# My_Smart_Home_Rev2_1.net
KiCad netlist of a schematic drawn in EAGLE
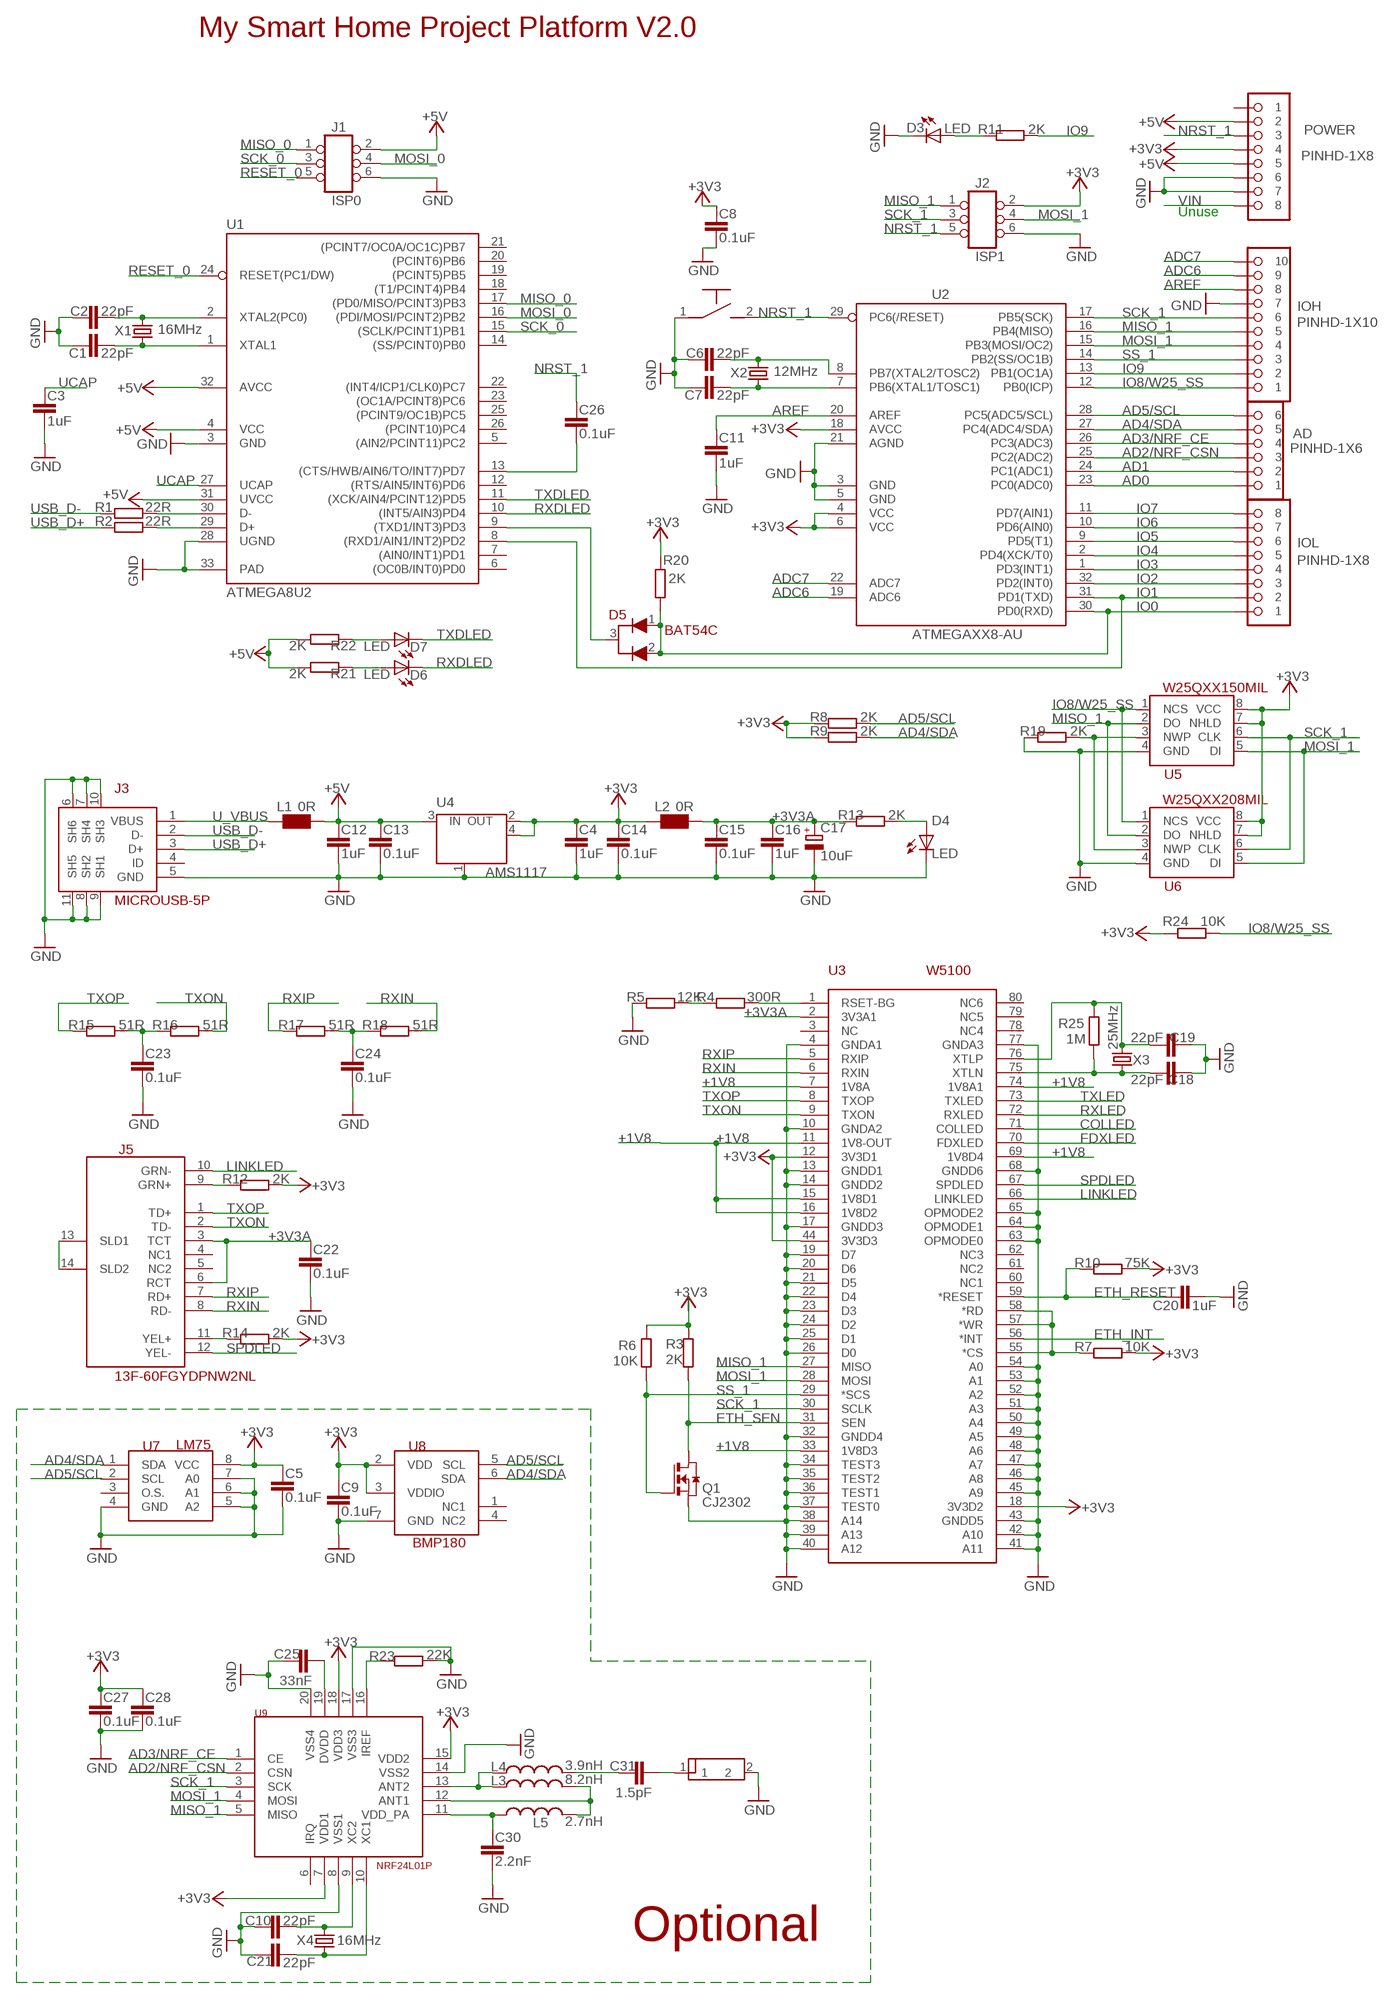
[diagram p0: schematic, sheet 1]

(export (version "E")
  (design (tool "Eeschema 10.0.6"))
  (components
    (comp (ref "AD")
      (value "PINHD-1X6")
      (footprint "eagle-import:1X06")
      (libsource (lib "eagle-import") (part "PINHD-1X6"))
    )
    (comp (ref "ANT1")
      (value "2.4G_ANT1")
      (footprint "eagle-import:2.4G_PCB_ANT")
      (libsource (lib "eagle-import") (part "2.4G_ANT1"))
    )
    (comp (ref "C1")
      (value "22pF")
      (footprint "eagle-import:C0603")
      (libsource (lib "eagle-import") (part "C-NP"))
    )
    (comp (ref "C2")
      (value "22pF")
      (footprint "eagle-import:C0603")
      (libsource (lib "eagle-import") (part "C-NP"))
    )
    (comp (ref "C3")
      (value "1uF")
      (footprint "eagle-import:C0603")
      (libsource (lib "eagle-import") (part "C-NP"))
    )
    (comp (ref "C4")
      (value "1uF")
      (footprint "eagle-import:C0603")
      (libsource (lib "eagle-import") (part "C-NP"))
    )
    (comp (ref "C5")
      (value "0.1uF")
      (footprint "eagle-import:C0603")
      (libsource (lib "eagle-import") (part "C-NP"))
    )
    (comp (ref "C6")
      (value "22pF")
      (footprint "eagle-import:C0603")
      (libsource (lib "eagle-import") (part "C-NP"))
    )
    (comp (ref "C7")
      (value "22pF")
      (footprint "eagle-import:C0603")
      (libsource (lib "eagle-import") (part "C-NP"))
    )
    (comp (ref "C8")
      (value "0.1uF")
      (footprint "eagle-import:C0603")
      (libsource (lib "eagle-import") (part "C-NP"))
    )
    (comp (ref "C9")
      (value "0.1uF")
      (footprint "eagle-import:C0603")
      (libsource (lib "eagle-import") (part "C-NP"))
    )
    (comp (ref "C10")
      (value "22pF")
      (footprint "eagle-import:C0603")
      (libsource (lib "eagle-import") (part "C-NP"))
    )
    (comp (ref "C11")
      (value "1uF")
      (footprint "eagle-import:C0603")
      (libsource (lib "eagle-import") (part "C-NP"))
    )
    (comp (ref "C12")
      (value "1uF")
      (footprint "eagle-import:C0603")
      (libsource (lib "eagle-import") (part "C-NP"))
    )
    (comp (ref "C13")
      (value "0.1uF")
      (footprint "eagle-import:C0603")
      (libsource (lib "eagle-import") (part "C-NP"))
    )
    (comp (ref "C14")
      (value "0.1uF")
      (footprint "eagle-import:C0603")
      (libsource (lib "eagle-import") (part "C-NP"))
    )
    (comp (ref "C15")
      (value "0.1uF")
      (footprint "eagle-import:C0603")
      (libsource (lib "eagle-import") (part "C-NP"))
    )
    (comp (ref "C16")
      (value "1uF")
      (footprint "eagle-import:C0603")
      (libsource (lib "eagle-import") (part "C-NP"))
    )
    (comp (ref "C17")
      (value "10uF")
      (footprint "eagle-import:C0805")
      (libsource (lib "eagle-import") (part "C-POL"))
    )
    (comp (ref "C18")
      (value "22pF")
      (footprint "eagle-import:C0603")
      (libsource (lib "eagle-import") (part "C-NP"))
    )
    (comp (ref "C19")
      (value "22pF")
      (footprint "eagle-import:C0603")
      (libsource (lib "eagle-import") (part "C-NP"))
    )
    (comp (ref "C20")
      (value "1uF")
      (footprint "eagle-import:C0603")
      (libsource (lib "eagle-import") (part "C-NP"))
    )
    (comp (ref "C21")
      (value "22pF")
      (footprint "eagle-import:C0603")
      (libsource (lib "eagle-import") (part "C-NP"))
    )
    (comp (ref "C22")
      (value "0.1uF")
      (footprint "eagle-import:C0603")
      (libsource (lib "eagle-import") (part "C-NP"))
    )
    (comp (ref "C23")
      (value "0.1uF")
      (footprint "eagle-import:C0603")
      (libsource (lib "eagle-import") (part "C-NP"))
    )
    (comp (ref "C24")
      (value "0.1uF")
      (footprint "eagle-import:C0603")
      (libsource (lib "eagle-import") (part "C-NP"))
    )
    (comp (ref "C25")
      (value "33nF")
      (footprint "eagle-import:C0603")
      (libsource (lib "eagle-import") (part "C-NP"))
    )
    (comp (ref "C26")
      (value "0.1uF")
      (footprint "eagle-import:C0603")
      (libsource (lib "eagle-import") (part "C-NP"))
    )
    (comp (ref "C27")
      (value "0.1uF")
      (footprint "eagle-import:C0603")
      (libsource (lib "eagle-import") (part "C-NP"))
    )
    (comp (ref "C28")
      (value "0.1uF")
      (footprint "eagle-import:C0603")
      (libsource (lib "eagle-import") (part "C-NP"))
    )
    (comp (ref "C30")
      (value "2.2nF")
      (footprint "eagle-import:C0603")
      (libsource (lib "eagle-import") (part "C-NP"))
    )
    (comp (ref "C31")
      (value "1.5pF")
      (footprint "eagle-import:C0603")
      (libsource (lib "eagle-import") (part "C-NP"))
    )
    (comp (ref "D3")
      (value "LED")
      (footprint "eagle-import:LED0805")
      (libsource (lib "eagle-import") (part "LED"))
    )
    (comp (ref "D4")
      (value "LED")
      (footprint "eagle-import:LED0805")
      (libsource (lib "eagle-import") (part "LED"))
    )
    (comp (ref "D5")
      (value "BAT54C")
      (footprint "eagle-import:SOT23")
      (libsource (lib "eagle-import") (part "BAT54C"))
    )
    (comp (ref "D6")
      (value "LED")
      (footprint "eagle-import:LED0805")
      (libsource (lib "eagle-import") (part "LED"))
    )
    (comp (ref "D7")
      (value "LED")
      (footprint "eagle-import:LED0805")
      (libsource (lib "eagle-import") (part "LED"))
    )
    (comp (ref "IOH")
      (value "PINHD-1X10")
      (footprint "eagle-import:1X10")
      (libsource (lib "eagle-import") (part "PINHD-1X10"))
    )
    (comp (ref "IOL")
      (value "PINHD-1X8")
      (footprint "eagle-import:1X08")
      (libsource (lib "eagle-import") (part "PINHD-1X8"))
    )
    (comp (ref "J1")
      (value "ISP0")
      (footprint "eagle-import:2X03")
      (libsource (lib "eagle-import") (part "PINHD-2X3"))
    )
    (comp (ref "J2")
      (value "ISP1")
      (footprint "eagle-import:2X03")
      (libsource (lib "eagle-import") (part "PINHD-2X3"))
    )
    (comp (ref "J3")
      (value "MICROUSB-5P")
      (footprint "eagle-import:MICROUSB-5P-SMD")
      (libsource (lib "eagle-import") (part "MICROUSB-5P"))
    )
    (comp (ref "J5")
      (value "13F-60FGYDPNW2NL")
      (footprint "eagle-import:13F-60FGYDPNW2NL")
      (libsource (lib "eagle-import") (part "13F-60FGYDPNW2NL"))
    )
    (comp (ref "L1")
      (value "0R")
      (footprint "eagle-import:R0603")
      (libsource (lib "eagle-import") (part "L_M"))
    )
    (comp (ref "L2")
      (value "0R")
      (footprint "eagle-import:R0603")
      (libsource (lib "eagle-import") (part "L_M"))
    )
    (comp (ref "L3")
      (value "8.2nH")
      (footprint "eagle-import:R0603")
      (libsource (lib "eagle-import") (part "L"))
    )
    (comp (ref "L4")
      (value "3.9nH")
      (footprint "eagle-import:R0603")
      (libsource (lib "eagle-import") (part "L"))
    )
    (comp (ref "L5")
      (value "2.7nH")
      (footprint "eagle-import:R0603")
      (libsource (lib "eagle-import") (part "L"))
    )
    (comp (ref "POWER")
      (value "PINHD-1X8")
      (footprint "eagle-import:1X08")
      (libsource (lib "eagle-import") (part "PINHD-1X8"))
    )
    (comp (ref "Q1")
      (value "CJ2302")
      (footprint "eagle-import:SOT23")
      (libsource (lib "eagle-import") (part "NMOS-SOT23"))
    )
    (comp (ref "R1")
      (value "22R")
      (footprint "eagle-import:R0603")
      (libsource (lib "eagle-import") (part "RES"))
    )
    (comp (ref "R2")
      (value "22R")
      (footprint "eagle-import:R0603")
      (libsource (lib "eagle-import") (part "RES"))
    )
    (comp (ref "R3")
      (value "2K")
      (footprint "eagle-import:R0603")
      (libsource (lib "eagle-import") (part "RES"))
    )
    (comp (ref "R4")
      (value "300R")
      (footprint "eagle-import:R0603")
      (libsource (lib "eagle-import") (part "RES"))
    )
    (comp (ref "R5")
      (value "12K")
      (footprint "eagle-import:R0603")
      (libsource (lib "eagle-import") (part "RES"))
    )
    (comp (ref "R6")
      (value "10K")
      (footprint "eagle-import:R0603")
      (libsource (lib "eagle-import") (part "RES"))
    )
    (comp (ref "R7")
      (value "10K")
      (footprint "eagle-import:R0603")
      (libsource (lib "eagle-import") (part "RES"))
    )
    (comp (ref "R8")
      (value "2K")
      (footprint "eagle-import:R0603")
      (libsource (lib "eagle-import") (part "RES"))
    )
    (comp (ref "R9")
      (value "2K")
      (footprint "eagle-import:R0603")
      (libsource (lib "eagle-import") (part "RES"))
    )
    (comp (ref "R10")
      (value "75K")
      (footprint "eagle-import:R0603")
      (libsource (lib "eagle-import") (part "RES"))
    )
    (comp (ref "R11")
      (value "2K")
      (footprint "eagle-import:R0603")
      (libsource (lib "eagle-import") (part "RES"))
    )
    (comp (ref "R12")
      (value "2K")
      (footprint "eagle-import:R0603")
      (libsource (lib "eagle-import") (part "RES"))
    )
    (comp (ref "R13")
      (value "2K")
      (footprint "eagle-import:R0603")
      (libsource (lib "eagle-import") (part "RES"))
    )
    (comp (ref "R14")
      (value "2K")
      (footprint "eagle-import:R0603")
      (libsource (lib "eagle-import") (part "RES"))
    )
    (comp (ref "R15")
      (value "51R")
      (footprint "eagle-import:R0603")
      (libsource (lib "eagle-import") (part "RES"))
    )
    (comp (ref "R16")
      (value "51R")
      (footprint "eagle-import:R0603")
      (libsource (lib "eagle-import") (part "RES"))
    )
    (comp (ref "R17")
      (value "51R")
      (footprint "eagle-import:R0603")
      (libsource (lib "eagle-import") (part "RES"))
    )
    (comp (ref "R18")
      (value "51R")
      (footprint "eagle-import:R0603")
      (libsource (lib "eagle-import") (part "RES"))
    )
    (comp (ref "R19")
      (value "2K")
      (footprint "eagle-import:R0603")
      (libsource (lib "eagle-import") (part "RES"))
    )
    (comp (ref "R20")
      (value "2K")
      (footprint "eagle-import:R0603")
      (libsource (lib "eagle-import") (part "RES"))
    )
    (comp (ref "R21")
      (value "2K")
      (footprint "eagle-import:R0603")
      (libsource (lib "eagle-import") (part "RES"))
    )
    (comp (ref "R22")
      (value "2K")
      (footprint "eagle-import:R0603")
      (libsource (lib "eagle-import") (part "RES"))
    )
    (comp (ref "R23")
      (value "22K")
      (footprint "eagle-import:R0603")
      (libsource (lib "eagle-import") (part "RES"))
    )
    (comp (ref "R24")
      (value "10K")
      (footprint "eagle-import:R0603")
      (libsource (lib "eagle-import") (part "RES"))
    )
    (comp (ref "R25")
      (value "1M")
      (footprint "eagle-import:R0603")
      (libsource (lib "eagle-import") (part "RES"))
    )
    (comp (ref "SW2")
      (value "SW-2")
      (footprint "eagle-import:SW-2P-SMD")
      (libsource (lib "eagle-import") (part "SW-2"))
    )
    (comp (ref "U1")
      (value "ATMEGA8U2")
      (footprint "eagle-import:MLF32")
      (libsource (lib "eagle-import") (part "ATMEGA8U2"))
    )
    (comp (ref "U2")
      (value "ATMEGAXX8-AU")
      (footprint "eagle-import:TQFP32-08")
      (libsource (lib "eagle-import") (part "ATMEGAXX8-AU"))
    )
    (comp (ref "U3")
      (value "W5100")
      (footprint "eagle-import:SQFP-S-10X10-80")
      (libsource (lib "eagle-import") (part "W5100"))
    )
    (comp (ref "U4")
      (value "AMS1117")
      (footprint "eagle-import:SOT223")
      (libsource (lib "eagle-import") (part "AMS1117"))
    )
    (comp (ref "U5")
      (value "W25QXX150MIL")
      (footprint "eagle-import:8S1")
      (libsource (lib "eagle-import") (part "W25QXX150MIL"))
    )
    (comp (ref "U6")
      (value "W25QXX208MIL")
      (footprint "eagle-import:8S2")
      (libsource (lib "eagle-import") (part "W25QXX208MIL"))
    )
    (comp (ref "U7")
      (value "LM75")
      (footprint "eagle-import:8S1")
      (libsource (lib "eagle-import") (part "LM75"))
    )
    (comp (ref "U8")
      (value "BMP180")
      (footprint "eagle-import:LGA-7P")
      (libsource (lib "eagle-import") (part "BMP180"))
    )
    (comp (ref "U9")
      (value "NRF24L01P")
      (footprint "eagle-import:QFN20")
      (libsource (lib "eagle-import") (part "NRF24L01P"))
    )
    (comp (ref "X1")
      (value "16MHz")
      (footprint "eagle-import:HC49UP")
      (libsource (lib "eagle-import") (part "CRYSTAL"))
    )
    (comp (ref "X2")
      (value "12MHz")
      (footprint "eagle-import:HC49UP")
      (libsource (lib "eagle-import") (part "CRYSTAL"))
    )
    (comp (ref "X3")
      (value "25MHz")
      (footprint "eagle-import:HC49UP")
      (libsource (lib "eagle-import") (part "CRYSTAL"))
    )
    (comp (ref "X4")
      (value "16MHz")
      (footprint "eagle-import:HC49UP")
      (libsource (lib "eagle-import") (part "CRYSTAL"))
    )
  )
  (nets
    (net (code "1") (name "+3V3") (class "Default")
      (node (ref "C14") (pin "2") (pinfunction "2_2") (pintype "passive"))
      (node (ref "C27") (pin "2") (pinfunction "2_2") (pintype "passive"))
      (node (ref "C28") (pin "2") (pinfunction "2_2") (pintype "passive"))
      (node (ref "C4") (pin "2") (pinfunction "2_2") (pintype "passive"))
      (node (ref "C5") (pin "2") (pinfunction "2_2") (pintype "passive"))
      (node (ref "C8") (pin "2") (pinfunction "2_2") (pintype "passive"))
      (node (ref "C9") (pin "2") (pinfunction "2_2") (pintype "passive"))
      (node (ref "J2") (pin "2") (pinfunction "2_2") (pintype "passive"))
      (node (ref "L2") (pin "1") (pinfunction "1_1") (pintype "passive"))
      (node (ref "POWER") (pin "4") (pinfunction "4_4") (pintype "passive"))
      (node (ref "R10") (pin "2") (pinfunction "2_2") (pintype "passive"))
      (node (ref "R12") (pin "1") (pinfunction "1_1") (pintype "passive"))
      (node (ref "R14") (pin "1") (pinfunction "1_1") (pintype "passive"))
      (node (ref "R20") (pin "2") (pinfunction "2_2") (pintype "passive"))
      (node (ref "R24") (pin "1") (pinfunction "1_1") (pintype "passive"))
      (node (ref "R3") (pin "2") (pinfunction "2_2") (pintype "passive"))
      (node (ref "R6") (pin "1") (pinfunction "1_1") (pintype "passive"))
      (node (ref "R7") (pin "2") (pinfunction "2_2") (pintype "passive"))
      (node (ref "R8") (pin "2") (pinfunction "2_2") (pintype "passive"))
      (node (ref "R9") (pin "2") (pinfunction "2_2") (pintype "passive"))
      (node (ref "U2") (pin "18") (pinfunction "AVCC_18") (pintype "bidirectional"))
      (node (ref "U2") (pin "4") (pinfunction "VCC_4") (pintype "bidirectional"))
      (node (ref "U2") (pin "6") (pinfunction "VCC_6") (pintype "bidirectional"))
      (node (ref "U3") (pin "12") (pinfunction "3V3D1_12") (pintype "power_in"))
      (node (ref "U3") (pin "18") (pinfunction "3V3D2_18") (pintype "power_in"))
      (node (ref "U3") (pin "44") (pinfunction "3V3D3_44") (pintype "power_in"))
      (node (ref "U4") (pin "2") (pinfunction "OUT_2") (pintype "passive"))
      (node (ref "U4") (pin "4") (pinfunction "OUT_4") (pintype "passive"))
      (node (ref "U5") (pin "7") (pinfunction "NHLD_7") (pintype "bidirectional"))
      (node (ref "U5") (pin "8") (pinfunction "VCC_8") (pintype "bidirectional"))
      (node (ref "U6") (pin "7") (pinfunction "NHLD_7") (pintype "bidirectional"))
      (node (ref "U6") (pin "8") (pinfunction "VCC_8") (pintype "bidirectional"))
      (node (ref "U7") (pin "8") (pinfunction "VCC_8") (pintype "bidirectional"))
      (node (ref "U8") (pin "2") (pinfunction "VDD_2") (pintype "bidirectional"))
      (node (ref "U8") (pin "3") (pinfunction "VDDIO_3") (pintype "bidirectional"))
      (node (ref "U9") (pin "15") (pinfunction "VDD2_15") (pintype "bidirectional"))
      (node (ref "U9") (pin "18") (pinfunction "VDD3_18") (pintype "bidirectional"))
      (node (ref "U9") (pin "7") (pinfunction "VDD1_7") (pintype "bidirectional"))
    )
    (net (code "2") (name "+5V") (class "Default")
      (node (ref "C12") (pin "2") (pinfunction "2_2") (pintype "passive"))
      (node (ref "C13") (pin "2") (pinfunction "2_2") (pintype "passive"))
      (node (ref "J1") (pin "2") (pinfunction "2_2") (pintype "passive"))
      (node (ref "L1") (pin "2") (pinfunction "2_2") (pintype "passive"))
      (node (ref "POWER") (pin "2") (pinfunction "2_2") (pintype "passive"))
      (node (ref "POWER") (pin "5") (pinfunction "5_5") (pintype "passive"))
      (node (ref "R21") (pin "1") (pinfunction "1_1") (pintype "passive"))
      (node (ref "R22") (pin "1") (pinfunction "1_1") (pintype "passive"))
      (node (ref "U1") (pin "31") (pinfunction "UVCC_31") (pintype "power_in"))
      (node (ref "U1") (pin "32") (pinfunction "AVCC_32") (pintype "power_in"))
      (node (ref "U1") (pin "4") (pinfunction "VCC_4") (pintype "power_in"))
      (node (ref "U4") (pin "3") (pinfunction "IN_3") (pintype "input"))
    )
    (net (code "3") (name "/+1V8") (class "Default")
      (node (ref "U3") (pin "11") (pinfunction "1V8-OUT_11") (pintype "power_in"))
      (node (ref "U3") (pin "15") (pinfunction "1V8D1_15") (pintype "power_in"))
      (node (ref "U3") (pin "16") (pinfunction "1V8D2_16") (pintype "power_in"))
      (node (ref "U3") (pin "33") (pinfunction "1V8D3_33") (pintype "power_in"))
      (node (ref "U3") (pin "69") (pinfunction "1V8D4_69") (pintype "power_in"))
      (node (ref "U3") (pin "7") (pinfunction "1V8A_7") (pintype "power_in"))
      (node (ref "U3") (pin "74") (pinfunction "1V8A1_74") (pintype "power_in"))
    )
    (net (code "4") (name "/+3V3A") (class "Default")
      (node (ref "C15") (pin "2") (pinfunction "2_2") (pintype "passive"))
      (node (ref "C16") (pin "2") (pinfunction "2_2") (pintype "passive"))
      (node (ref "C17") (pin "1") (pinfunction "+_1") (pintype "passive"))
      (node (ref "C22") (pin "2") (pinfunction "2_2") (pintype "passive"))
      (node (ref "J5") (pin "3") (pinfunction "TCT_3") (pintype "bidirectional"))
      (node (ref "J5") (pin "6") (pinfunction "RCT_6") (pintype "bidirectional"))
      (node (ref "L2") (pin "2") (pinfunction "2_2") (pintype "passive"))
      (node (ref "R13") (pin "2") (pinfunction "2_2") (pintype "passive"))
      (node (ref "U3") (pin "2") (pinfunction "3V3A1_2") (pintype "power_in"))
    )
    (net (code "5") (name "/AD0") (class "Default")
      (node (ref "AD") (pin "1") (pinfunction "1_1") (pintype "passive"))
      (node (ref "U2") (pin "23") (pinfunction "PC0(ADC0)_23") (pintype "bidirectional"))
    )
    (net (code "6") (name "/AD1") (class "Default")
      (node (ref "AD") (pin "2") (pinfunction "2_2") (pintype "passive"))
      (node (ref "U2") (pin "24") (pinfunction "PC1(ADC1)_24") (pintype "bidirectional"))
    )
    (net (code "7") (name "/AD2{slash}NRF_CSN") (class "Default")
      (node (ref "AD") (pin "3") (pinfunction "3_3") (pintype "passive"))
      (node (ref "U2") (pin "25") (pinfunction "PC2(ADC2)_25") (pintype "bidirectional"))
      (node (ref "U9") (pin "2") (pinfunction "CSN_2") (pintype "bidirectional"))
    )
    (net (code "8") (name "/AD3{slash}NRF_CE") (class "Default")
      (node (ref "AD") (pin "4") (pinfunction "4_4") (pintype "passive"))
      (node (ref "U2") (pin "26") (pinfunction "PC3(ADC3)_26") (pintype "bidirectional"))
      (node (ref "U9") (pin "1") (pinfunction "CE_1") (pintype "bidirectional"))
    )
    (net (code "9") (name "/AD4{slash}SDA") (class "Default")
      (node (ref "AD") (pin "5") (pinfunction "5_5") (pintype "passive"))
      (node (ref "R9") (pin "1") (pinfunction "1_1") (pintype "passive"))
      (node (ref "U2") (pin "27") (pinfunction "PC4(ADC4/SDA)_27") (pintype "bidirectional"))
      (node (ref "U7") (pin "1") (pinfunction "SDA_1") (pintype "bidirectional"))
      (node (ref "U8") (pin "6") (pinfunction "SDA_6") (pintype "bidirectional"))
    )
    (net (code "10") (name "/AD5{slash}SCL") (class "Default")
      (node (ref "AD") (pin "6") (pinfunction "6_6") (pintype "passive"))
      (node (ref "R8") (pin "1") (pinfunction "1_1") (pintype "passive"))
      (node (ref "U2") (pin "28") (pinfunction "PC5(ADC5/SCL)_28") (pintype "bidirectional"))
      (node (ref "U7") (pin "2") (pinfunction "SCL_2") (pintype "bidirectional"))
      (node (ref "U8") (pin "5") (pinfunction "SCL_5") (pintype "bidirectional"))
    )
    (net (code "11") (name "/ADC6") (class "Default")
      (node (ref "IOH") (pin "9") (pinfunction "9_9") (pintype "passive"))
      (node (ref "U2") (pin "19") (pinfunction "ADC6_19") (pintype "bidirectional"))
    )
    (net (code "12") (name "/ADC7") (class "Default")
      (node (ref "IOH") (pin "10") (pinfunction "10_10") (pintype "passive"))
      (node (ref "U2") (pin "22") (pinfunction "ADC7_22") (pintype "bidirectional"))
    )
    (net (code "13") (name "/AREF") (class "Default")
      (node (ref "C11") (pin "2") (pinfunction "2_2") (pintype "passive"))
      (node (ref "IOH") (pin "8") (pinfunction "8_8") (pintype "passive"))
      (node (ref "U2") (pin "20") (pinfunction "AREF_20") (pintype "bidirectional"))
    )
    (net (code "14") (name "/COLLED") (class "Default")
      (node (ref "U3") (pin "71") (pinfunction "COLLED_71") (pintype "output"))
    )
    (net (code "15") (name "/ETH_INT") (class "Default")
      (node (ref "U3") (pin "56") (pinfunction "*INT_56") (pintype "input"))
    )
    (net (code "16") (name "/ETH_RESET") (class "Default")
      (node (ref "C20") (pin "2") (pinfunction "2_2") (pintype "passive"))
      (node (ref "R10") (pin "1") (pinfunction "1_1") (pintype "passive"))
      (node (ref "U3") (pin "59") (pinfunction "*RESET_59") (pintype "input"))
    )
    (net (code "17") (name "/ETH_SEN") (class "Default")
      (node (ref "Q1") (pin "3") (pinfunction "D_3") (pintype "passive"))
      (node (ref "R3") (pin "1") (pinfunction "1_1") (pintype "passive"))
      (node (ref "U3") (pin "31") (pinfunction "SEN_31") (pintype "input"))
    )
    (net (code "18") (name "/FDXLED") (class "Default")
      (node (ref "U3") (pin "70") (pinfunction "FDXLED_70") (pintype "output"))
    )
    (net (code "19") (name "/IO0") (class "Default")
      (node (ref "D5") (pin "1") (pinfunction "1_1") (pintype "bidirectional"))
      (node (ref "D5") (pin "2") (pinfunction "2_2") (pintype "bidirectional"))
      (node (ref "IOL") (pin "1") (pinfunction "1_1") (pintype "passive"))
      (node (ref "R20") (pin "1") (pinfunction "1_1") (pintype "passive"))
      (node (ref "U2") (pin "30") (pinfunction "PD0(RXD)_30") (pintype "bidirectional"))
    )
    (net (code "20") (name "/IO1") (class "Default")
      (node (ref "IOL") (pin "2") (pinfunction "2_2") (pintype "passive"))
      (node (ref "U1") (pin "8") (pinfunction "(RXD1/AIN1/INT2)PD2_8") (pintype "bidirectional"))
      (node (ref "U2") (pin "31") (pinfunction "PD1(TXD)_31") (pintype "bidirectional"))
    )
    (net (code "21") (name "/IO2") (class "Default")
      (node (ref "IOL") (pin "3") (pinfunction "3_3") (pintype "passive"))
      (node (ref "U2") (pin "32") (pinfunction "PD2(INT0)_32") (pintype "bidirectional"))
    )
    (net (code "22") (name "/IO3") (class "Default")
      (node (ref "IOL") (pin "4") (pinfunction "4_4") (pintype "passive"))
      (node (ref "U2") (pin "1") (pinfunction "PD3(INT1)_1") (pintype "bidirectional"))
    )
    (net (code "23") (name "/IO4") (class "Default")
      (node (ref "IOL") (pin "5") (pinfunction "5_5") (pintype "passive"))
      (node (ref "U2") (pin "2") (pinfunction "PD4(XCK/T0)_2") (pintype "bidirectional"))
    )
    (net (code "24") (name "/IO5") (class "Default")
      (node (ref "IOL") (pin "6") (pinfunction "6_6") (pintype "passive"))
      (node (ref "U2") (pin "9") (pinfunction "PD5(T1)_9") (pintype "bidirectional"))
    )
    (net (code "25") (name "/IO6") (class "Default")
      (node (ref "IOL") (pin "7") (pinfunction "7_7") (pintype "passive"))
      (node (ref "U2") (pin "10") (pinfunction "PD6(AIN0)_10") (pintype "bidirectional"))
    )
    (net (code "26") (name "/IO7") (class "Default")
      (node (ref "IOL") (pin "8") (pinfunction "8_8") (pintype "passive"))
      (node (ref "U2") (pin "11") (pinfunction "PD7(AIN1)_11") (pintype "bidirectional"))
    )
    (net (code "27") (name "/IO8{slash}W25_SS") (class "Default")
      (node (ref "IOH") (pin "1") (pinfunction "1_1") (pintype "passive"))
      (node (ref "R24") (pin "2") (pinfunction "2_2") (pintype "passive"))
      (node (ref "U2") (pin "12") (pinfunction "PB0(ICP)_12") (pintype "bidirectional"))
      (node (ref "U5") (pin "1") (pinfunction "NCS_1") (pintype "bidirectional"))
      (node (ref "U6") (pin "1") (pinfunction "NCS_1") (pintype "bidirectional"))
    )
    (net (code "28") (name "/IO9") (class "Default")
      (node (ref "IOH") (pin "2") (pinfunction "2_2") (pintype "passive"))
      (node (ref "R11") (pin "1") (pinfunction "1_1") (pintype "passive"))
      (node (ref "U2") (pin "13") (pinfunction "PB1(OC1A)_13") (pintype "bidirectional"))
    )
    (net (code "29") (name "/LINKLED") (class "Default")
      (node (ref "J5") (pin "10") (pinfunction "GRN-_10") (pintype "bidirectional"))
      (node (ref "U3") (pin "66") (pinfunction "LINKLED_66") (pintype "output"))
    )
    (net (code "30") (name "/MISO_0") (class "Default")
      (node (ref "J1") (pin "1") (pinfunction "1_1") (pintype "passive"))
      (node (ref "U1") (pin "17") (pinfunction "(PD0/MISO/PCINT3)PB3_17") (pintype "bidirectional"))
    )
    (net (code "31") (name "/MISO_1") (class "Default")
      (node (ref "IOH") (pin "5") (pinfunction "5_5") (pintype "passive"))
      (node (ref "J2") (pin "1") (pinfunction "1_1") (pintype "passive"))
      (node (ref "U2") (pin "16") (pinfunction "PB4(MISO)_16") (pintype "bidirectional"))
      (node (ref "U3") (pin "27") (pinfunction "MISO_27") (pintype "input"))
      (node (ref "U5") (pin "2") (pinfunction "DO_2") (pintype "bidirectional"))
      (node (ref "U6") (pin "2") (pinfunction "DO_2") (pintype "bidirectional"))
      (node (ref "U9") (pin "5") (pinfunction "MISO_5") (pintype "bidirectional"))
    )
    (net (code "32") (name "/MOSI_0") (class "Default")
      (node (ref "J1") (pin "4") (pinfunction "4_4") (pintype "passive"))
      (node (ref "U1") (pin "16") (pinfunction "(PDI/MOSI/PCINT2)PB2_16") (pintype "bidirectional"))
    )
    (net (code "33") (name "/MOSI_1") (class "Default")
      (node (ref "IOH") (pin "4") (pinfunction "4_4") (pintype "passive"))
      (node (ref "J2") (pin "4") (pinfunction "4_4") (pintype "passive"))
      (node (ref "U2") (pin "15") (pinfunction "PB3(MOSI/OC2)_15") (pintype "bidirectional"))
      (node (ref "U3") (pin "28") (pinfunction "MOSI_28") (pintype "output"))
      (node (ref "U5") (pin "5") (pinfunction "DI_5") (pintype "bidirectional"))
      (node (ref "U6") (pin "5") (pinfunction "DI_5") (pintype "bidirectional"))
      (node (ref "U9") (pin "4") (pinfunction "MOSI_4") (pintype "bidirectional"))
    )
    (net (code "34") (name "/NRST_1") (class "Default")
      (node (ref "C26") (pin "2") (pinfunction "2_2") (pintype "passive"))
      (node (ref "J2") (pin "5") (pinfunction "5_5") (pintype "passive"))
      (node (ref "POWER") (pin "3") (pinfunction "3_3") (pintype "passive"))
      (node (ref "SW2") (pin "2") (pinfunction "P$2_2") (pintype "bidirectional"))
      (node (ref "U2") (pin "29") (pinfunction "PC6(/RESET)_29") (pintype "bidirectional"))
    )
    (net (code "35") (name "/RESET_0") (class "Default")
      (node (ref "J1") (pin "5") (pinfunction "5_5") (pintype "passive"))
      (node (ref "U1") (pin "24") (pinfunction "RESET(PC1/DW)_24") (pintype "input"))
    )
    (net (code "36") (name "/RXDLED") (class "Default")
      (node (ref "D6") (pin "C") (pinfunction "C_C") (pintype "passive"))
      (node (ref "U1") (pin "10") (pinfunction "(INT5/AIN3)PD4_10") (pintype "bidirectional"))
    )
    (net (code "37") (name "/RXIN") (class "Default")
      (node (ref "J5") (pin "8") (pinfunction "RD-_8") (pintype "bidirectional"))
      (node (ref "R18") (pin "1") (pinfunction "1_1") (pintype "passive"))
      (node (ref "U3") (pin "6") (pinfunction "RXIN_6") (pintype "input"))
    )
    (net (code "38") (name "/RXIP") (class "Default")
      (node (ref "J5") (pin "7") (pinfunction "RD+_7") (pintype "bidirectional"))
      (node (ref "R17") (pin "2") (pinfunction "2_2") (pintype "passive"))
      (node (ref "U3") (pin "5") (pinfunction "RXIP_5") (pintype "input"))
    )
    (net (code "39") (name "/RXLED") (class "Default")
      (node (ref "U3") (pin "72") (pinfunction "RXLED_72") (pintype "output"))
    )
    (net (code "40") (name "/SCK_0") (class "Default")
      (node (ref "J1") (pin "3") (pinfunction "3_3") (pintype "passive"))
      (node (ref "U1") (pin "15") (pinfunction "(SCLK/PCINT1)PB1_15") (pintype "bidirectional"))
    )
    (net (code "41") (name "/SCK_1") (class "Default")
      (node (ref "IOH") (pin "6") (pinfunction "6_6") (pintype "passive"))
      (node (ref "J2") (pin "3") (pinfunction "3_3") (pintype "passive"))
      (node (ref "U2") (pin "17") (pinfunction "PB5(SCK)_17") (pintype "bidirectional"))
      (node (ref "U3") (pin "30") (pinfunction "SCLK_30") (pintype "input"))
      (node (ref "U5") (pin "6") (pinfunction "CLK_6") (pintype "bidirectional"))
      (node (ref "U6") (pin "6") (pinfunction "CLK_6") (pintype "bidirectional"))
      (node (ref "U9") (pin "3") (pinfunction "SCK_3") (pintype "bidirectional"))
    )
    (net (code "42") (name "/SPDLED") (class "Default")
      (node (ref "J5") (pin "12") (pinfunction "YEL-_12") (pintype "bidirectional"))
      (node (ref "U3") (pin "67") (pinfunction "SPDLED_67") (pintype "output"))
    )
    (net (code "43") (name "/SS_1") (class "Default")
      (node (ref "IOH") (pin "3") (pinfunction "3_3") (pintype "passive"))
      (node (ref "Q1") (pin "1") (pinfunction "G_1") (pintype "passive"))
      (node (ref "R6") (pin "2") (pinfunction "2_2") (pintype "passive"))
      (node (ref "U2") (pin "14") (pinfunction "PB2(SS/OC1B)_14") (pintype "bidirectional"))
      (node (ref "U3") (pin "29") (pinfunction "*SCS_29") (pintype "input"))
    )
    (net (code "44") (name "/TXDLED") (class "Default")
      (node (ref "D7") (pin "C") (pinfunction "C_C") (pintype "passive"))
      (node (ref "U1") (pin "11") (pinfunction "(XCK/AIN4/PCINT12)PD5_11") (pintype "bidirectional"))
    )
    (net (code "45") (name "/TXLED") (class "Default")
      (node (ref "U3") (pin "73") (pinfunction "TXLED_73") (pintype "output"))
    )
    (net (code "46") (name "/TXON") (class "Default")
      (node (ref "J5") (pin "2") (pinfunction "TD-_2") (pintype "bidirectional"))
      (node (ref "R16") (pin "1") (pinfunction "1_1") (pintype "passive"))
      (node (ref "U3") (pin "9") (pinfunction "TXON_9") (pintype "output"))
    )
    (net (code "47") (name "/TXOP") (class "Default")
      (node (ref "J5") (pin "1") (pinfunction "TD+_1") (pintype "bidirectional"))
      (node (ref "R15") (pin "2") (pinfunction "2_2") (pintype "passive"))
      (node (ref "U3") (pin "8") (pinfunction "TXOP_8") (pintype "output"))
    )
    (net (code "48") (name "/UCAP") (class "Default")
      (node (ref "C3") (pin "2") (pinfunction "2_2") (pintype "passive"))
      (node (ref "U1") (pin "27") (pinfunction "UCAP_27") (pintype "passive"))
    )
    (net (code "49") (name "/USB_D+") (class "Default")
      (node (ref "J3") (pin "3") (pinfunction "D+_3") (pintype "bidirectional"))
      (node (ref "R2") (pin "1") (pinfunction "1_1") (pintype "passive"))
    )
    (net (code "50") (name "/USB_D-") (class "Default")
      (node (ref "J3") (pin "2") (pinfunction "D-_2") (pintype "bidirectional"))
      (node (ref "R1") (pin "1") (pinfunction "1_1") (pintype "passive"))
    )
    (net (code "51") (name "/U_VBUS") (class "Default")
      (node (ref "J3") (pin "1") (pinfunction "VBUS_1") (pintype "bidirectional"))
      (node (ref "L1") (pin "1") (pinfunction "1_1") (pintype "passive"))
    )
    (net (code "52") (name "/VIN") (class "Default")
      (node (ref "POWER") (pin "8") (pinfunction "8_8") (pintype "passive"))
    )
    (net (code "53") (name "GND") (class "Default")
      (node (ref "ANT1") (pin "2") (pinfunction "2_2") (pintype "bidirectional"))
      (node (ref "C1") (pin "1") (pinfunction "1_1") (pintype "passive"))
      (node (ref "C10") (pin "1") (pinfunction "1_1") (pintype "passive"))
      (node (ref "C11") (pin "1") (pinfunction "1_1") (pintype "passive"))
      (node (ref "C12") (pin "1") (pinfunction "1_1") (pintype "passive"))
      (node (ref "C13") (pin "1") (pinfunction "1_1") (pintype "passive"))
      (node (ref "C14") (pin "1") (pinfunction "1_1") (pintype "passive"))
      (node (ref "C15") (pin "1") (pinfunction "1_1") (pintype "passive"))
      (node (ref "C16") (pin "1") (pinfunction "1_1") (pintype "passive"))
      (node (ref "C17") (pin "2") (pinfunction "-_2") (pintype "passive"))
      (node (ref "C18") (pin "1") (pinfunction "1_1") (pintype "passive"))
      (node (ref "C19") (pin "1") (pinfunction "1_1") (pintype "passive"))
      (node (ref "C2") (pin "1") (pinfunction "1_1") (pintype "passive"))
      (node (ref "C20") (pin "1") (pinfunction "1_1") (pintype "passive"))
      (node (ref "C21") (pin "1") (pinfunction "1_1") (pintype "passive"))
      (node (ref "C22") (pin "1") (pinfunction "1_1") (pintype "passive"))
      (node (ref "C23") (pin "1") (pinfunction "1_1") (pintype "passive"))
      (node (ref "C24") (pin "1") (pinfunction "1_1") (pintype "passive"))
      (node (ref "C25") (pin "2") (pinfunction "2_2") (pintype "passive"))
      (node (ref "C27") (pin "1") (pinfunction "1_1") (pintype "passive"))
      (node (ref "C28") (pin "1") (pinfunction "1_1") (pintype "passive"))
      (node (ref "C3") (pin "1") (pinfunction "1_1") (pintype "passive"))
      (node (ref "C30") (pin "1") (pinfunction "1_1") (pintype "passive"))
      (node (ref "C4") (pin "1") (pinfunction "1_1") (pintype "passive"))
      (node (ref "C5") (pin "1") (pinfunction "1_1") (pintype "passive"))
      (node (ref "C6") (pin "1") (pinfunction "1_1") (pintype "passive"))
      (node (ref "C7") (pin "1") (pinfunction "1_1") (pintype "passive"))
      (node (ref "C8") (pin "1") (pinfunction "1_1") (pintype "passive"))
      (node (ref "C9") (pin "1") (pinfunction "1_1") (pintype "passive"))
      (node (ref "D3") (pin "C") (pinfunction "C_C") (pintype "passive"))
      (node (ref "D4") (pin "C") (pinfunction "C_C") (pintype "passive"))
      (node (ref "IOH") (pin "7") (pinfunction "7_7") (pintype "passive"))
      (node (ref "J1") (pin "6") (pinfunction "6_6") (pintype "passive"))
      (node (ref "J2") (pin "6") (pinfunction "6_6") (pintype "passive"))
      (node (ref "J3") (pin "10") (pinfunction "SH3_10") (pintype "bidirectional"))
      (node (ref "J3") (pin "11") (pinfunction "SH5_11") (pintype "bidirectional"))
      (node (ref "J3") (pin "5") (pinfunction "GND_5") (pintype "bidirectional"))
      (node (ref "J3") (pin "6") (pinfunction "SH6_6") (pintype "bidirectional"))
      (node (ref "J3") (pin "7") (pinfunction "SH4_7") (pintype "bidirectional"))
      (node (ref "J3") (pin "8") (pinfunction "SH2_8") (pintype "bidirectional"))
      (node (ref "J3") (pin "9") (pinfunction "SH1_9") (pintype "bidirectional"))
      (node (ref "POWER") (pin "6") (pinfunction "6_6") (pintype "passive"))
      (node (ref "POWER") (pin "7") (pinfunction "7_7") (pintype "passive"))
      (node (ref "Q1") (pin "2") (pinfunction "S_2") (pintype "passive"))
      (node (ref "R19") (pin "2") (pinfunction "2_2") (pintype "passive"))
      (node (ref "R23") (pin "1") (pinfunction "1_1") (pintype "passive"))
      (node (ref "R5") (pin "1") (pinfunction "1_1") (pintype "passive"))
      (node (ref "SW2") (pin "1") (pinfunction "P$1_1") (pintype "bidirectional"))
      (node (ref "U1") (pin "28") (pinfunction "UGND_28") (pintype "power_in"))
      (node (ref "U1") (pin "3") (pinfunction "GND_3") (pintype "power_in"))
      (node (ref "U1") (pin "33") (pinfunction "PAD_33") (pintype "power_in"))
      (node (ref "U2") (pin "21") (pinfunction "AGND_21") (pintype "bidirectional"))
      (node (ref "U2") (pin "3") (pinfunction "GND_3") (pintype "bidirectional"))
      (node (ref "U2") (pin "5") (pinfunction "GND_5") (pintype "bidirectional"))
      (node (ref "U3") (pin "10") (pinfunction "GNDA2_10") (pintype "power_in"))
      (node (ref "U3") (pin "13") (pinfunction "GNDD1_13") (pintype "power_in"))
      (node (ref "U3") (pin "14") (pinfunction "GNDD2_14") (pintype "power_in"))
      (node (ref "U3") (pin "17") (pinfunction "GNDD3_17") (pintype "power_in"))
      (node (ref "U3") (pin "19") (pinfunction "D7_19") (pintype "input"))
      (node (ref "U3") (pin "20") (pinfunction "D6_20") (pintype "input"))
      (node (ref "U3") (pin "21") (pinfunction "D5_21") (pintype "input"))
      (node (ref "U3") (pin "22") (pinfunction "D4_22") (pintype "input"))
      (node (ref "U3") (pin "23") (pinfunction "D3_23") (pintype "input"))
      (node (ref "U3") (pin "24") (pinfunction "D2_24") (pintype "input"))
      (node (ref "U3") (pin "25") (pinfunction "D1_25") (pintype "input"))
      (node (ref "U3") (pin "26") (pinfunction "D0_26") (pintype "input"))
      (node (ref "U3") (pin "32") (pinfunction "GNDD4_32") (pintype "power_in"))
      (node (ref "U3") (pin "34") (pinfunction "TEST3_34") (pintype "input"))
      (node (ref "U3") (pin "35") (pinfunction "TEST2_35") (pintype "input"))
      (node (ref "U3") (pin "36") (pinfunction "TEST1_36") (pintype "input"))
      (node (ref "U3") (pin "37") (pinfunction "TEST0_37") (pintype "input"))
      (node (ref "U3") (pin "38") (pinfunction "A14_38") (pintype "input"))
      (node (ref "U3") (pin "39") (pinfunction "A13_39") (pintype "input"))
      (node (ref "U3") (pin "4") (pinfunction "GNDA1_4") (pintype "power_in"))
      (node (ref "U3") (pin "40") (pinfunction "A12_40") (pintype "input"))
      (node (ref "U3") (pin "41") (pinfunction "A11_41") (pintype "input"))
      (node (ref "U3") (pin "42") (pinfunction "A10_42") (pintype "input"))
      (node (ref "U3") (pin "43") (pinfunction "GNDD5_43") (pintype "power_in"))
      (node (ref "U3") (pin "45") (pinfunction "A9_45") (pintype "input"))
      (node (ref "U3") (pin "46") (pinfunction "A8_46") (pintype "input"))
      (node (ref "U3") (pin "47") (pinfunction "A7_47") (pintype "input"))
      (node (ref "U3") (pin "48") (pinfunction "A6_48") (pintype "input"))
      (node (ref "U3") (pin "49") (pinfunction "A5_49") (pintype "input"))
      (node (ref "U3") (pin "50") (pinfunction "A4_50") (pintype "input"))
      (node (ref "U3") (pin "51") (pinfunction "A3_51") (pintype "input"))
      (node (ref "U3") (pin "52") (pinfunction "A2_52") (pintype "input"))
      (node (ref "U3") (pin "53") (pinfunction "A1_53") (pintype "input"))
      (node (ref "U3") (pin "54") (pinfunction "A0_54") (pintype "input"))
      (node (ref "U3") (pin "63") (pinfunction "OPMODE0_63") (pintype "input"))
      (node (ref "U3") (pin "64") (pinfunction "OPMODE1_64") (pintype "input"))
      (node (ref "U3") (pin "65") (pinfunction "OPMODE2_65") (pintype "input"))
      (node (ref "U3") (pin "68") (pinfunction "GNDD6_68") (pintype "power_in"))
      (node (ref "U3") (pin "77") (pinfunction "GNDA3_77") (pintype "power_in"))
      (node (ref "U4") (pin "1") (pinfunction "GND/ADJ_1") (pintype "input"))
      (node (ref "U5") (pin "4") (pinfunction "GND_4") (pintype "bidirectional"))
      (node (ref "U6") (pin "4") (pinfunction "GND_4") (pintype "bidirectional"))
      (node (ref "U7") (pin "4") (pinfunction "GND_4") (pintype "bidirectional"))
      (node (ref "U7") (pin "5") (pinfunction "A2_5") (pintype "bidirectional"))
      (node (ref "U7") (pin "6") (pinfunction "A1_6") (pintype "bidirectional"))
      (node (ref "U7") (pin "7") (pinfunction "A0_7") (pintype "bidirectional"))
      (node (ref "U8") (pin "7") (pinfunction "GND_7") (pintype "bidirectional"))
      (node (ref "U9") (pin "14") (pinfunction "VSS2_14") (pintype "bidirectional"))
      (node (ref "U9") (pin "17") (pinfunction "VSS3_17") (pintype "bidirectional"))
      (node (ref "U9") (pin "20") (pinfunction "VSS4_20") (pintype "bidirectional"))
      (node (ref "U9") (pin "8") (pinfunction "VSS1_8") (pintype "bidirectional"))
    )
    (net (code "54") (name "Net-(ANT1-Pad1)") (class "Default")
      (node (ref "ANT1") (pin "1") (pinfunction "1_1") (pintype "bidirectional"))
      (node (ref "C31") (pin "1") (pinfunction "1_1") (pintype "passive"))
    )
    (net (code "55") (name "Net-(C23-Pad2)") (class "Default")
      (node (ref "C23") (pin "2") (pinfunction "2_2") (pintype "passive"))
      (node (ref "R15") (pin "1") (pinfunction "1_1") (pintype "passive"))
      (node (ref "R16") (pin "2") (pinfunction "2_2") (pintype "passive"))
    )
    (net (code "56") (name "Net-(C24-Pad2)") (class "Default")
      (node (ref "C24") (pin "2") (pinfunction "2_2") (pintype "passive"))
      (node (ref "R17") (pin "1") (pinfunction "1_1") (pintype "passive"))
      (node (ref "R18") (pin "2") (pinfunction "2_2") (pintype "passive"))
    )
    (net (code "57") (name "Net-(C31-Pad2)") (class "Default")
      (node (ref "C31") (pin "2") (pinfunction "2_2") (pintype "passive"))
      (node (ref "L4") (pin "2") (pinfunction "2_2") (pintype "passive"))
    )
    (net (code "58") (name "Net-(D3-PadA)") (class "Default")
      (node (ref "D3") (pin "A") (pinfunction "A_A") (pintype "passive"))
      (node (ref "R11") (pin "2") (pinfunction "2_2") (pintype "passive"))
    )
    (net (code "59") (name "Net-(D4-PadA)") (class "Default")
      (node (ref "D4") (pin "A") (pinfunction "A_A") (pintype "passive"))
      (node (ref "R13") (pin "1") (pinfunction "1_1") (pintype "passive"))
    )
    (net (code "60") (name "Net-(D6-PadA)") (class "Default")
      (node (ref "D6") (pin "A") (pinfunction "A_A") (pintype "passive"))
      (node (ref "R21") (pin "2") (pinfunction "2_2") (pintype "passive"))
    )
    (net (code "61") (name "Net-(D7-PadA)") (class "Default")
      (node (ref "D7") (pin "A") (pinfunction "A_A") (pintype "passive"))
      (node (ref "R22") (pin "2") (pinfunction "2_2") (pintype "passive"))
    )
    (net (code "62") (name "Net-(J5-GRN+)") (class "Default")
      (node (ref "J5") (pin "9") (pinfunction "GRN+_9") (pintype "bidirectional"))
      (node (ref "R12") (pin "2") (pinfunction "2_2") (pintype "passive"))
    )
    (net (code "63") (name "Net-(J5-SLD1)") (class "Default")
      (node (ref "J5") (pin "13") (pinfunction "SLD1_13") (pintype "bidirectional"))
      (node (ref "J5") (pin "14") (pinfunction "SLD2_14") (pintype "bidirectional"))
    )
    (net (code "64") (name "Net-(J5-YEL+)") (class "Default")
      (node (ref "J5") (pin "11") (pinfunction "YEL+_11") (pintype "bidirectional"))
      (node (ref "R14") (pin "2") (pinfunction "2_2") (pintype "passive"))
    )
    (net (code "65") (name "Net-(R4-Pad1)") (class "Default")
      (node (ref "R4") (pin "1") (pinfunction "1_1") (pintype "passive"))
      (node (ref "R5") (pin "2") (pinfunction "2_2") (pintype "passive"))
    )
    (net (code "66") (name "Net-(U1-(CTS{slash}HWB{slash}AIN6{slash}TO{slash}INT7)PD7)") (class "Default")
      (node (ref "C26") (pin "1") (pinfunction "1_1") (pintype "passive"))
      (node (ref "U1") (pin "13") (pinfunction "(CTS/HWB/AIN6/TO/INT7)PD7_13") (pintype "bidirectional"))
    )
    (net (code "67") (name "Net-(U1-(TXD1{slash}INT3)PD3)") (class "Default")
      (node (ref "D5") (pin "3") (pinfunction "3_3") (pintype "bidirectional"))
      (node (ref "U1") (pin "9") (pinfunction "(TXD1/INT3)PD3_9") (pintype "bidirectional"))
    )
    (net (code "68") (name "Net-(U1-D+)") (class "Default")
      (node (ref "R2") (pin "2") (pinfunction "2_2") (pintype "passive"))
      (node (ref "U1") (pin "29") (pinfunction "D+_29") (pintype "bidirectional"))
    )
    (net (code "69") (name "Net-(U1-D-)") (class "Default")
      (node (ref "R1") (pin "2") (pinfunction "2_2") (pintype "passive"))
      (node (ref "U1") (pin "30") (pinfunction "D-_30") (pintype "bidirectional"))
    )
    (net (code "70") (name "Net-(U1-XTAL1)") (class "Default")
      (node (ref "C1") (pin "2") (pinfunction "2_2") (pintype "passive"))
      (node (ref "U1") (pin "1") (pinfunction "XTAL1_1") (pintype "bidirectional"))
      (node (ref "X1") (pin "1") (pinfunction "1_1") (pintype "passive"))
    )
    (net (code "71") (name "Net-(U1-XTAL2(PC0))") (class "Default")
      (node (ref "C2") (pin "2") (pinfunction "2_2") (pintype "passive"))
      (node (ref "U1") (pin "2") (pinfunction "XTAL2(PC0)_2") (pintype "bidirectional"))
      (node (ref "X1") (pin "2") (pinfunction "2_2") (pintype "passive"))
    )
    (net (code "72") (name "Net-(U2-PB6(XTAL1{slash}TOSC1))") (class "Default")
      (node (ref "C7") (pin "2") (pinfunction "2_2") (pintype "passive"))
      (node (ref "U2") (pin "7") (pinfunction "PB6(XTAL1/TOSC1)_7") (pintype "bidirectional"))
      (node (ref "X2") (pin "1") (pinfunction "1_1") (pintype "passive"))
    )
    (net (code "73") (name "Net-(U2-PB7(XTAL2{slash}TOSC2))") (class "Default")
      (node (ref "C6") (pin "2") (pinfunction "2_2") (pintype "passive"))
      (node (ref "U2") (pin "8") (pinfunction "PB7(XTAL2/TOSC2)_8") (pintype "bidirectional"))
      (node (ref "X2") (pin "2") (pinfunction "2_2") (pintype "passive"))
    )
    (net (code "74") (name "Net-(U3-*CS)") (class "Default")
      (node (ref "R7") (pin "1") (pinfunction "1_1") (pintype "passive"))
      (node (ref "U3") (pin "55") (pinfunction "*CS_55") (pintype "input"))
      (node (ref "U3") (pin "57") (pinfunction "*WR_57") (pintype "input"))
      (node (ref "U3") (pin "58") (pinfunction "*RD_58") (pintype "input"))
    )
    (net (code "75") (name "Net-(U3-RSET-BG)") (class "Default")
      (node (ref "R4") (pin "2") (pinfunction "2_2") (pintype "passive"))
      (node (ref "U3") (pin "1") (pinfunction "RSET-BG_1") (pintype "input"))
    )
    (net (code "76") (name "Net-(U3-XTLN)") (class "Default")
      (node (ref "C18") (pin "2") (pinfunction "2_2") (pintype "passive"))
      (node (ref "R25") (pin "2") (pinfunction "2_2") (pintype "passive"))
      (node (ref "U3") (pin "75") (pinfunction "XTLN_75") (pintype "output"))
      (node (ref "X3") (pin "2") (pinfunction "2_2") (pintype "passive"))
    )
    (net (code "77") (name "Net-(U3-XTLP)") (class "Default")
      (node (ref "C19") (pin "2") (pinfunction "2_2") (pintype "passive"))
      (node (ref "R25") (pin "1") (pinfunction "1_1") (pintype "passive"))
      (node (ref "U3") (pin "76") (pinfunction "XTLP_76") (pintype "output"))
      (node (ref "X3") (pin "1") (pinfunction "1_1") (pintype "passive"))
    )
    (net (code "78") (name "Net-(U5-NWP)") (class "Default")
      (node (ref "R19") (pin "1") (pinfunction "1_1") (pintype "passive"))
      (node (ref "U5") (pin "3") (pinfunction "NWP_3") (pintype "bidirectional"))
      (node (ref "U6") (pin "3") (pinfunction "NWP_3") (pintype "bidirectional"))
    )
    (net (code "79") (name "Net-(U9-ANT1)") (class "Default")
      (node (ref "L3") (pin "2") (pinfunction "2_2") (pintype "passive"))
      (node (ref "L5") (pin "2") (pinfunction "2_2") (pintype "passive"))
      (node (ref "U9") (pin "12") (pinfunction "ANT1_12") (pintype "bidirectional"))
    )
    (net (code "80") (name "Net-(U9-ANT2)") (class "Default")
      (node (ref "L3") (pin "1") (pinfunction "1_1") (pintype "passive"))
      (node (ref "L4") (pin "1") (pinfunction "1_1") (pintype "passive"))
      (node (ref "U9") (pin "13") (pinfunction "ANT2_13") (pintype "bidirectional"))
    )
    (net (code "81") (name "Net-(U9-DVDD)") (class "Default")
      (node (ref "C25") (pin "1") (pinfunction "1_1") (pintype "passive"))
      (node (ref "U9") (pin "19") (pinfunction "DVDD_19") (pintype "bidirectional"))
    )
    (net (code "82") (name "Net-(U9-IREF)") (class "Default")
      (node (ref "R23") (pin "2") (pinfunction "2_2") (pintype "passive"))
      (node (ref "U9") (pin "16") (pinfunction "IREF_16") (pintype "bidirectional"))
    )
    (net (code "83") (name "Net-(U9-VDD_PA)") (class "Default")
      (node (ref "C30") (pin "2") (pinfunction "2_2") (pintype "passive"))
      (node (ref "L5") (pin "1") (pinfunction "1_1") (pintype "passive"))
      (node (ref "U9") (pin "11") (pinfunction "VDD_PA_11") (pintype "bidirectional"))
    )
    (net (code "84") (name "Net-(U9-XC1)") (class "Default")
      (node (ref "C21") (pin "2") (pinfunction "2_2") (pintype "passive"))
      (node (ref "U9") (pin "10") (pinfunction "XC1_10") (pintype "bidirectional"))
      (node (ref "X4") (pin "1") (pinfunction "1_1") (pintype "passive"))
    )
    (net (code "85") (name "Net-(U9-XC2)") (class "Default")
      (node (ref "C10") (pin "2") (pinfunction "2_2") (pintype "passive"))
      (node (ref "U9") (pin "9") (pinfunction "XC2_9") (pintype "bidirectional"))
      (node (ref "X4") (pin "2") (pinfunction "2_2") (pintype "passive"))
    )
    (net (code "86") (name "unconnected-(J3-ID-Pad4)") (class "Default")
      (node (ref "J3") (pin "4") (pinfunction "ID_4") (pintype "bidirectional"))
    )
    (net (code "87") (name "unconnected-(J5-NC1-Pad4)") (class "Default")
      (node (ref "J5") (pin "4") (pinfunction "NC1_4") (pintype "bidirectional"))
    )
    (net (code "88") (name "unconnected-(J5-NC2-Pad5)") (class "Default")
      (node (ref "J5") (pin "5") (pinfunction "NC2_5") (pintype "bidirectional"))
    )
    (net (code "89") (name "unconnected-(POWER-Pad1)") (class "Default")
      (node (ref "POWER") (pin "1") (pinfunction "1_1") (pintype "passive"))
    )
    (net (code "90") (name "unconnected-(U1-(AIN0{slash}INT1)PD1-Pad7)") (class "Default")
      (node (ref "U1") (pin "7") (pinfunction "(AIN0/INT1)PD1_7") (pintype "bidirectional"))
    )
    (net (code "91") (name "unconnected-(U1-(AIN2{slash}PCINT11)PC2-Pad5)") (class "Default")
      (node (ref "U1") (pin "5") (pinfunction "(AIN2/PCINT11)PC2_5") (pintype "bidirectional"))
    )
    (net (code "92") (name "unconnected-(U1-(INT4{slash}ICP1{slash}CLK0)PC7-Pad22)") (class "Default")
      (node (ref "U1") (pin "22") (pinfunction "(INT4/ICP1/CLK0)PC7_22") (pintype "bidirectional"))
    )
    (net (code "93") (name "unconnected-(U1-(OC0B{slash}INT0)PD0-Pad6)") (class "Default")
      (node (ref "U1") (pin "6") (pinfunction "(OC0B/INT0)PD0_6") (pintype "bidirectional"))
    )
    (net (code "94") (name "unconnected-(U1-(OC1A{slash}PCINT8)PC6-Pad23)") (class "Default")
      (node (ref "U1") (pin "23") (pinfunction "(OC1A/PCINT8)PC6_23") (pintype "bidirectional"))
    )
    (net (code "95") (name "unconnected-(U1-(PCINT5)PB5-Pad19)") (class "Default")
      (node (ref "U1") (pin "19") (pinfunction "(PCINT5)PB5_19") (pintype "bidirectional"))
    )
    (net (code "96") (name "unconnected-(U1-(PCINT6)PB6-Pad20)") (class "Default")
      (node (ref "U1") (pin "20") (pinfunction "(PCINT6)PB6_20") (pintype "bidirectional"))
    )
    (net (code "97") (name "unconnected-(U1-(PCINT7{slash}OC0A{slash}OC1C)PB7-Pad21)") (class "Default")
      (node (ref "U1") (pin "21") (pinfunction "(PCINT7/OC0A/OC1C)PB7_21") (pintype "bidirectional"))
    )
    (net (code "98") (name "unconnected-(U1-(PCINT9{slash}OC1B)PC5-Pad25)") (class "Default")
      (node (ref "U1") (pin "25") (pinfunction "(PCINT9/OC1B)PC5_25") (pintype "bidirectional"))
    )
    (net (code "99") (name "unconnected-(U1-(PCINT10)PC4-Pad26)") (class "Default")
      (node (ref "U1") (pin "26") (pinfunction "(PCINT10)PC4_26") (pintype "bidirectional"))
    )
    (net (code "100") (name "unconnected-(U1-(RTS{slash}AIN5{slash}INT6)PD6-Pad12)") (class "Default")
      (node (ref "U1") (pin "12") (pinfunction "(RTS/AIN5/INT6)PD6_12") (pintype "bidirectional"))
    )
    (net (code "101") (name "unconnected-(U1-(SS{slash}PCINT0)PB0-Pad14)") (class "Default")
      (node (ref "U1") (pin "14") (pinfunction "(SS/PCINT0)PB0_14") (pintype "bidirectional"))
    )
    (net (code "102") (name "unconnected-(U1-(T1{slash}PCINT4)PB4-Pad18)") (class "Default")
      (node (ref "U1") (pin "18") (pinfunction "(T1/PCINT4)PB4_18") (pintype "bidirectional"))
    )
    (net (code "103") (name "unconnected-(U3-NC-Pad3)") (class "Default")
      (node (ref "U3") (pin "3") (pinfunction "NC_3") (pintype "no_connect"))
    )
    (net (code "104") (name "unconnected-(U3-NC1-Pad60)") (class "Default")
      (node (ref "U3") (pin "60") (pinfunction "NC1_60") (pintype "no_connect"))
    )
    (net (code "105") (name "unconnected-(U3-NC2-Pad61)") (class "Default")
      (node (ref "U3") (pin "61") (pinfunction "NC2_61") (pintype "no_connect"))
    )
    (net (code "106") (name "unconnected-(U3-NC3-Pad62)") (class "Default")
      (node (ref "U3") (pin "62") (pinfunction "NC3_62") (pintype "no_connect"))
    )
    (net (code "107") (name "unconnected-(U3-NC4-Pad78)") (class "Default")
      (node (ref "U3") (pin "78") (pinfunction "NC4_78") (pintype "no_connect"))
    )
    (net (code "108") (name "unconnected-(U3-NC5-Pad79)") (class "Default")
      (node (ref "U3") (pin "79") (pinfunction "NC5_79") (pintype "no_connect"))
    )
    (net (code "109") (name "unconnected-(U3-NC6-Pad80)") (class "Default")
      (node (ref "U3") (pin "80") (pinfunction "NC6_80") (pintype "no_connect"))
    )
    (net (code "110") (name "unconnected-(U7-O.S.-Pad3)") (class "Default")
      (node (ref "U7") (pin "3") (pinfunction "O.S._3") (pintype "bidirectional"))
    )
    (net (code "111") (name "unconnected-(U8-NC1-Pad1)") (class "Default")
      (node (ref "U8") (pin "1") (pinfunction "NC1_1") (pintype "bidirectional"))
    )
    (net (code "112") (name "unconnected-(U8-NC2-Pad4)") (class "Default")
      (node (ref "U8") (pin "4") (pinfunction "NC2_4") (pintype "bidirectional"))
    )
    (net (code "113") (name "unconnected-(U9-IRQ-Pad6)") (class "Default")
      (node (ref "U9") (pin "6") (pinfunction "IRQ_6") (pintype "bidirectional"))
    )
  )
)
